# STM-power-boot.net
KiCad netlist of a schematic drawn in Altium Designer
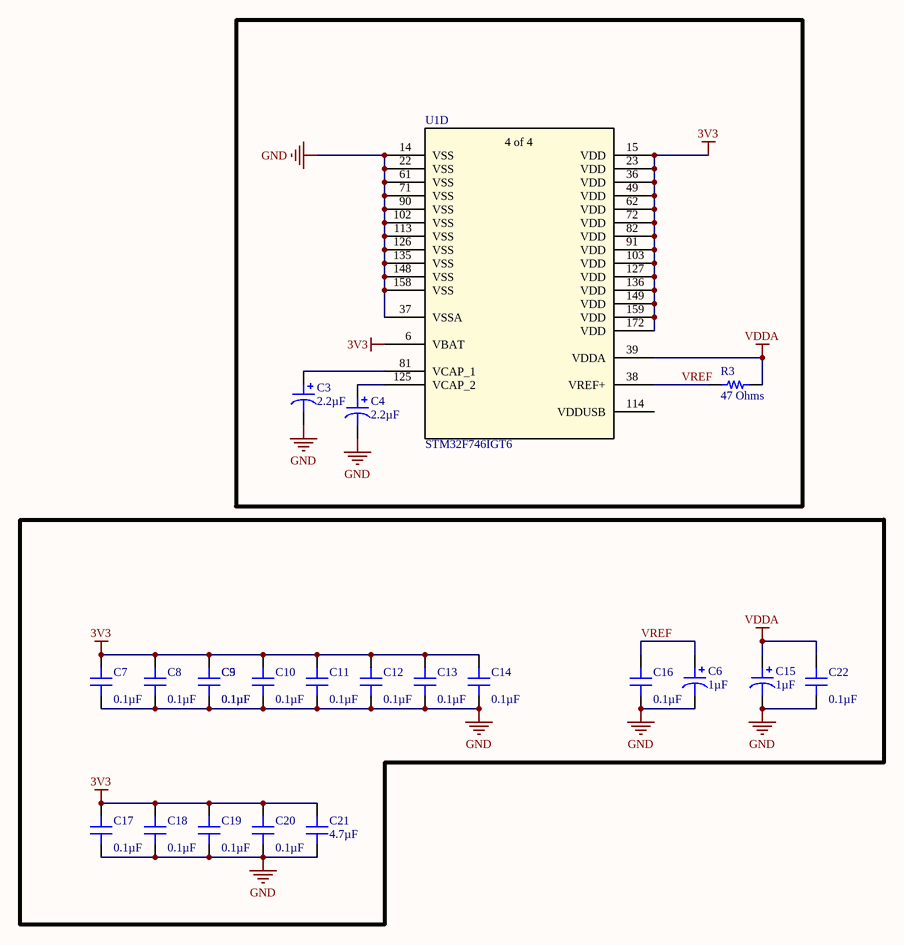
[diagram p0: STM-power-boot.SchDoc]

(export (version "E")
  (design (tool "Eeschema 10.0.6"))
  (components
    (comp (ref "C3")
      (value "2.2µF")
      (footprint "CAP POL 1411_3528")
      (description "CAP TANT 2.2UF 20% 16V 1411")
      (fields (field (name "PART NUMBER") "T496B225M016ATE3K5") (field (name "MANUFACTURER") "KEMET"))
      (libsource (lib "Celestial Altium Library - altium_library") (part "Polarised Capacitor"))
    )
    (comp (ref "C4")
      (value "2.2µF")
      (footprint "CAP POL 1411_3528")
      (description "CAP TANT 2.2UF 20% 16V 1411")
      (fields (field (name "PART NUMBER") "T496B225M016ATE3K5") (field (name "MANUFACTURER") "KEMET"))
      (libsource (lib "Celestial Altium Library - altium_library") (part "Polarised Capacitor"))
    )
    (comp (ref "C5")
      (value "0.1µF")
      (footprint "CAP 0603_1608")
      (description "CAP CER 0.1UF 6.3V X7R 0603")
      (fields (field (name "PART NUMBER") "6R3X14W104MV4T"))
      (libsource (lib "Celestial Altium Library - altium_library") (part "Capacitor"))
    )
    (comp (ref "C6")
      (value "1µF")
      (footprint "CAP POL 1206_3216")
      (description "CAP TANT 1UF 20% 16V 1206")
      (fields (field (name "PART NUMBER") "T494A105M016AT") (field (name "MANUFACTURER") "KEMET"))
      (libsource (lib "Celestial Altium Library - altium_library") (part "Polarised Capacitor"))
    )
    (comp (ref "C7")
      (value "0.1µF")
      (footprint "CAP 0603_1608")
      (description "CAP CER 0.1UF 6.3V X7R 0603")
      (fields (field (name "PART NUMBER") "6R3X14W104MV4T"))
      (libsource (lib "Celestial Altium Library - altium_library") (part "Capacitor"))
    )
    (comp (ref "C8")
      (value "0.1µF")
      (footprint "CAP 0603_1608")
      (description "CAP CER 0.1UF 6.3V X7R 0603")
      (fields (field (name "PART NUMBER") "6R3X14W104MV4T"))
      (libsource (lib "Celestial Altium Library - altium_library") (part "Capacitor"))
    )
    (comp (ref "C9")
      (value "0.1µF")
      (footprint "CAP 0603_1608")
      (description "CAP CER 0.1UF 6.3V X7R 0603")
      (fields (field (name "PART NUMBER") "6R3X14W104MV4T"))
      (libsource (lib "Celestial Altium Library - altium_library") (part "Capacitor"))
    )
    (comp (ref "C10")
      (value "0.1µF")
      (footprint "CAP 0603_1608")
      (description "CAP CER 0.1UF 6.3V X7R 0603")
      (fields (field (name "PART NUMBER") "6R3X14W104MV4T"))
      (libsource (lib "Celestial Altium Library - altium_library") (part "Capacitor"))
    )
    (comp (ref "C11")
      (value "0.1µF")
      (footprint "CAP 0603_1608")
      (description "CAP CER 0.1UF 6.3V X7R 0603")
      (fields (field (name "PART NUMBER") "6R3X14W104MV4T"))
      (libsource (lib "Celestial Altium Library - altium_library") (part "Capacitor"))
    )
    (comp (ref "C12")
      (value "0.1µF")
      (footprint "CAP 0603_1608")
      (description "CAP CER 0.1UF 6.3V X7R 0603")
      (fields (field (name "PART NUMBER") "6R3X14W104MV4T"))
      (libsource (lib "Celestial Altium Library - altium_library") (part "Capacitor"))
    )
    (comp (ref "C13")
      (value "0.1µF")
      (footprint "CAP 0603_1608")
      (description "CAP CER 0.1UF 6.3V X7R 0603")
      (fields (field (name "PART NUMBER") "6R3X14W104MV4T"))
      (libsource (lib "Celestial Altium Library - altium_library") (part "Capacitor"))
    )
    (comp (ref "C14")
      (value "0.1µF")
      (footprint "CAP 0603_1608")
      (description "CAP CER 0.1UF 6.3V X7R 0603")
      (fields (field (name "PART NUMBER") "6R3X14W104MV4T"))
      (libsource (lib "Celestial Altium Library - altium_library") (part "Capacitor"))
    )
    (comp (ref "C15")
      (value "1µF")
      (footprint "CAP POL 1206_3216")
      (description "CAP TANT 1UF 20% 16V 1206")
      (fields (field (name "PART NUMBER") "T494A105M016AT") (field (name "MANUFACTURER") "KEMET"))
      (libsource (lib "Celestial Altium Library - altium_library") (part "Polarised Capacitor"))
    )
    (comp (ref "C16")
      (value "0.1µF")
      (footprint "CAP 0603_1608")
      (description "CAP CER 0.1UF 6.3V X7R 0603")
      (fields (field (name "PART NUMBER") "6R3X14W104MV4T"))
      (libsource (lib "Celestial Altium Library - altium_library") (part "Capacitor"))
    )
    (comp (ref "C17")
      (value "0.1µF")
      (footprint "CAP 0603_1608")
      (description "CAP CER 0.1UF 6.3V X7R 0603")
      (fields (field (name "PART NUMBER") "6R3X14W104MV4T"))
      (libsource (lib "Celestial Altium Library - altium_library") (part "Capacitor"))
    )
    (comp (ref "C18")
      (value "0.1µF")
      (footprint "CAP 0603_1608")
      (description "CAP CER 0.1UF 6.3V X7R 0603")
      (fields (field (name "PART NUMBER") "6R3X14W104MV4T"))
      (libsource (lib "Celestial Altium Library - altium_library") (part "Capacitor"))
    )
    (comp (ref "C19")
      (value "0.1µF")
      (footprint "CAP 0603_1608")
      (description "CAP CER 0.1UF 6.3V X7R 0603")
      (fields (field (name "PART NUMBER") "6R3X14W104MV4T"))
      (libsource (lib "Celestial Altium Library - altium_library") (part "Capacitor"))
    )
    (comp (ref "C20")
      (value "0.1µF")
      (footprint "CAP 0603_1608")
      (description "CAP CER 0.1UF 6.3V X7R 0603")
      (fields (field (name "PART NUMBER") "6R3X14W104MV4T"))
      (libsource (lib "Celestial Altium Library - altium_library") (part "Capacitor"))
    )
    (comp (ref "C21")
      (value "4.7µF")
      (footprint "CAP 0603_1608")
      (description "CAP CER 4.7UF 6.3V X5R 0603")
      (fields (field (name "PART NUMBER") "C0603C475K9PACTU"))
      (libsource (lib "Celestial Altium Library - altium_library") (part "Capacitor"))
    )
    (comp (ref "C22")
      (value "0.1µF")
      (footprint "CAP 0603_1608")
      (description "CAP CER 0.1UF 6.3V X7R 0603")
      (fields (field (name "PART NUMBER") "6R3X14W104MV4T"))
      (libsource (lib "Celestial Altium Library - altium_library") (part "Capacitor"))
    )
    (comp (ref "R3")
      (value "47 Ohms")
      (footprint "RES 0805_2012")
      (description "CRGP 0805 47R 1%")
      (fields
        (field (name "PART NUMBER") "CRGP0805F47R")
        (field (name "MANUFACTURER") "TE Connectivity Passive Product")
      )
      (libsource (lib "Celestial Altium Library - altium_library") (part "Resistor"))
    )
    (comp (ref "U1")
      (value "STM32F746IGT6")
      (footprint "LQFP176_24X24_STM")
      (description "No Description Available")
      (fields (field (name "COPYRIGHT") "Copyright (C) 2018 Accelerated Designs. All rights reserved"))
      (libsource (lib "hy-smt") (part "STM32F746IGT6"))
    )
  )
  (nets
    (net (code "1") (name "/VREF") (class "Default")
      (node (ref "C16") (pin "2") (pinfunction "2_2") (pintype "passive"))
      (node (ref "C6") (pin "1") (pinfunction "1_1") (pintype "passive"))
      (node (ref "R3") (pin "2") (pinfunction "2_2") (pintype "passive"))
      (node (ref "U1") (pin "38") (pinfunction "VREF+_38") (pintype "power_in"))
    )
    (net (code "2") (name "3V3") (class "Default")
      (node (ref "C10") (pin "2") (pinfunction "2_2") (pintype "passive"))
      (node (ref "C11") (pin "2") (pinfunction "2_2") (pintype "passive"))
      (node (ref "C12") (pin "2") (pinfunction "2_2") (pintype "passive"))
      (node (ref "C13") (pin "2") (pinfunction "2_2") (pintype "passive"))
      (node (ref "C14") (pin "2") (pinfunction "2_2") (pintype "passive"))
      (node (ref "C17") (pin "2") (pinfunction "2_2") (pintype "passive"))
      (node (ref "C18") (pin "2") (pinfunction "2_2") (pintype "passive"))
      (node (ref "C19") (pin "2") (pinfunction "2_2") (pintype "passive"))
      (node (ref "C20") (pin "2") (pinfunction "2_2") (pintype "passive"))
      (node (ref "C21") (pin "2") (pinfunction "2_2") (pintype "passive"))
      (node (ref "C5") (pin "2") (pinfunction "2_2") (pintype "passive"))
      (node (ref "C7") (pin "2") (pinfunction "2_2") (pintype "passive"))
      (node (ref "C8") (pin "2") (pinfunction "2_2") (pintype "passive"))
      (node (ref "C9") (pin "2") (pinfunction "2_2") (pintype "passive"))
      (node (ref "U1") (pin "103") (pinfunction "VDD_103") (pintype "power_in"))
      (node (ref "U1") (pin "127") (pinfunction "VDD_127") (pintype "power_in"))
      (node (ref "U1") (pin "136") (pinfunction "VDD_136") (pintype "power_in"))
      (node (ref "U1") (pin "149") (pinfunction "VDD_149") (pintype "power_in"))
      (node (ref "U1") (pin "15") (pinfunction "VDD_15") (pintype "power_in"))
      (node (ref "U1") (pin "159") (pinfunction "VDD_159") (pintype "power_in"))
      (node (ref "U1") (pin "172") (pinfunction "VDD_172") (pintype "power_in"))
      (node (ref "U1") (pin "23") (pinfunction "VDD_23") (pintype "power_in"))
      (node (ref "U1") (pin "36") (pinfunction "VDD_36") (pintype "power_in"))
      (node (ref "U1") (pin "49") (pinfunction "VDD_49") (pintype "power_in"))
      (node (ref "U1") (pin "6") (pinfunction "VBAT_6") (pintype "power_in"))
      (node (ref "U1") (pin "62") (pinfunction "VDD_62") (pintype "power_in"))
      (node (ref "U1") (pin "72") (pinfunction "VDD_72") (pintype "power_in"))
      (node (ref "U1") (pin "82") (pinfunction "VDD_82") (pintype "power_in"))
      (node (ref "U1") (pin "91") (pinfunction "VDD_91") (pintype "power_in"))
    )
    (net (code "3") (name "GND") (class "Default")
      (node (ref "C10") (pin "1") (pinfunction "1_1") (pintype "passive"))
      (node (ref "C11") (pin "1") (pinfunction "1_1") (pintype "passive"))
      (node (ref "C12") (pin "1") (pinfunction "1_1") (pintype "passive"))
      (node (ref "C13") (pin "1") (pinfunction "1_1") (pintype "passive"))
      (node (ref "C14") (pin "1") (pinfunction "1_1") (pintype "passive"))
      (node (ref "C15") (pin "2") (pinfunction "2_2") (pintype "passive"))
      (node (ref "C16") (pin "1") (pinfunction "1_1") (pintype "passive"))
      (node (ref "C17") (pin "1") (pinfunction "1_1") (pintype "passive"))
      (node (ref "C18") (pin "1") (pinfunction "1_1") (pintype "passive"))
      (node (ref "C19") (pin "1") (pinfunction "1_1") (pintype "passive"))
      (node (ref "C20") (pin "1") (pinfunction "1_1") (pintype "passive"))
      (node (ref "C21") (pin "1") (pinfunction "1_1") (pintype "passive"))
      (node (ref "C22") (pin "1") (pinfunction "1_1") (pintype "passive"))
      (node (ref "C3") (pin "2") (pinfunction "2_2") (pintype "passive"))
      (node (ref "C4") (pin "2") (pinfunction "2_2") (pintype "passive"))
      (node (ref "C5") (pin "1") (pinfunction "1_1") (pintype "passive"))
      (node (ref "C6") (pin "2") (pinfunction "2_2") (pintype "passive"))
      (node (ref "C7") (pin "1") (pinfunction "1_1") (pintype "passive"))
      (node (ref "C8") (pin "1") (pinfunction "1_1") (pintype "passive"))
      (node (ref "C9") (pin "1") (pinfunction "1_1") (pintype "passive"))
      (node (ref "U1") (pin "102") (pinfunction "VSS_102") (pintype "power_in"))
      (node (ref "U1") (pin "113") (pinfunction "VSS_113") (pintype "power_in"))
      (node (ref "U1") (pin "126") (pinfunction "VSS_126") (pintype "power_in"))
      (node (ref "U1") (pin "135") (pinfunction "VSS_135") (pintype "power_in"))
      (node (ref "U1") (pin "14") (pinfunction "VSS_14") (pintype "power_in"))
      (node (ref "U1") (pin "148") (pinfunction "VSS_148") (pintype "power_in"))
      (node (ref "U1") (pin "158") (pinfunction "VSS_158") (pintype "power_in"))
      (node (ref "U1") (pin "22") (pinfunction "VSS_22") (pintype "power_in"))
      (node (ref "U1") (pin "37") (pinfunction "VSSA_37") (pintype "power_in"))
      (node (ref "U1") (pin "61") (pinfunction "VSS_61") (pintype "power_in"))
      (node (ref "U1") (pin "71") (pinfunction "VSS_71") (pintype "power_in"))
      (node (ref "U1") (pin "90") (pinfunction "VSS_90") (pintype "power_in"))
    )
    (net (code "4") (name "Net-(U1D-VCAP_1)") (class "Default")
      (node (ref "C3") (pin "1") (pinfunction "1_1") (pintype "passive"))
      (node (ref "U1") (pin "81") (pinfunction "VCAP_1_81") (pintype "power_in"))
    )
    (net (code "5") (name "Net-(U1D-VCAP_2)") (class "Default")
      (node (ref "C4") (pin "1") (pinfunction "1_1") (pintype "passive"))
      (node (ref "U1") (pin "125") (pinfunction "VCAP_2_125") (pintype "power_in"))
    )
    (net (code "6") (name "VDDA") (class "Default")
      (node (ref "C15") (pin "1") (pinfunction "1_1") (pintype "passive"))
      (node (ref "C22") (pin "2") (pinfunction "2_2") (pintype "passive"))
      (node (ref "R3") (pin "1") (pinfunction "1_1") (pintype "passive"))
      (node (ref "U1") (pin "39") (pinfunction "VDDA_39") (pintype "power_in"))
    )
    (net (code "7") (name "unconnected-(U1D-VDDUSB-Pad114)") (class "Default")
      (node (ref "U1") (pin "114") (pinfunction "VDDUSB_114") (pintype "power_in"))
    )
  )
)
